# schematic.net
KiCad netlist of a schematic drawn in EAGLE
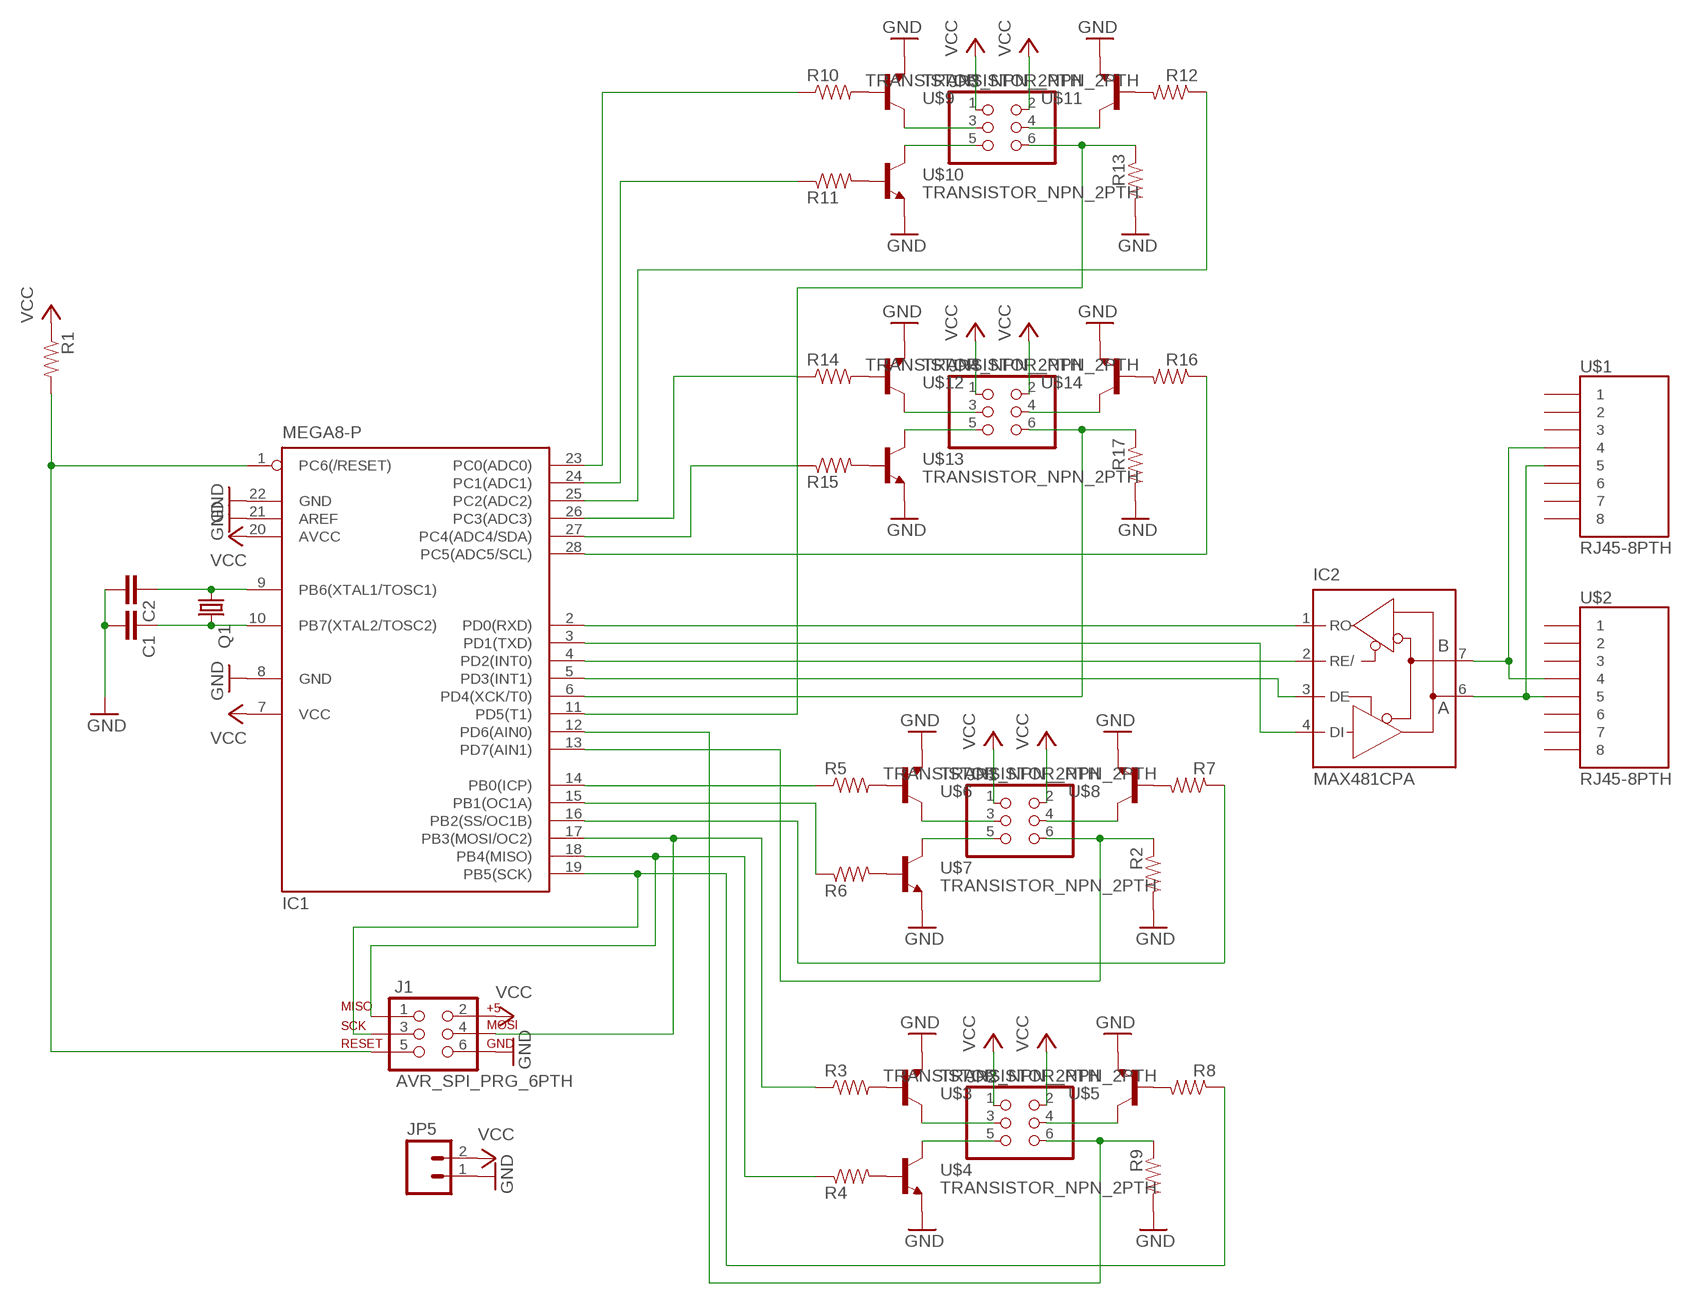
[diagram p0: schematic, sheet 1]

(export (version "E")
  (design (tool "Eeschema 10.0.6"))
  (components
    (comp (ref "C1")
      (value "CAPKIT")
      (footprint "eagle-import:CAP-PTH-SMALL-KIT")
      (libsource (lib "eagle-import") (part "CAPKIT"))
    )
    (comp (ref "C2")
      (value "CAPKIT")
      (footprint "eagle-import:CAP-PTH-SMALL-KIT")
      (libsource (lib "eagle-import") (part "CAPKIT"))
    )
    (comp (ref "IC1")
      (value "MEGA8-P")
      (footprint "eagle-import:DIL28-3")
      (libsource (lib "eagle-import") (part "MEGA8-P"))
    )
    (comp (ref "IC2")
      (value "MAX481CPA")
      (footprint "eagle-import:DIL08")
      (fields (field (name "MPN") "MAX481CPA+"))
      (libsource (lib "eagle-import") (part "MAX481CPA"))
    )
    (comp (ref "J1")
      (value "AVR_SPI_PRG_6PTH")
      (footprint "eagle-import:2X3")
      (libsource (lib "eagle-import") (part "AVR_SPI_PRG_6PTH"))
    )
    (comp (ref "JP1")
      (value "PINHD-2X3")
      (footprint "eagle-import:2X03")
      (libsource (lib "eagle-import") (part "PINHD-2X3"))
    )
    (comp (ref "JP2")
      (value "PINHD-2X3")
      (footprint "eagle-import:2X03")
      (libsource (lib "eagle-import") (part "PINHD-2X3"))
    )
    (comp (ref "JP3")
      (value "PINHD-2X3")
      (footprint "eagle-import:2X03")
      (libsource (lib "eagle-import") (part "PINHD-2X3"))
    )
    (comp (ref "JP4")
      (value "PINHD-2X3")
      (footprint "eagle-import:2X03")
      (libsource (lib "eagle-import") (part "PINHD-2X3"))
    )
    (comp (ref "JP5")
      (value "M023.5MM")
      (footprint "eagle-import:SCREWTERMINAL-3.5MM-2")
      (libsource (lib "eagle-import") (part "M023.5MM"))
    )
    (comp (ref "Q1")
      (value "CRYSTALHC49U-V")
      (footprint "eagle-import:HC49U-V")
      (libsource (lib "eagle-import") (part "CRYSTALHC49U-V"))
    )
    (comp (ref "R1")
      (value "RESISTORPTH-1/4W")
      (footprint "eagle-import:AXIAL-0.4")
      (libsource (lib "eagle-import") (part "RESISTORPTH-1/4W"))
    )
    (comp (ref "R2")
      (value "RESISTORPTH-1/4W")
      (footprint "eagle-import:AXIAL-0.4")
      (libsource (lib "eagle-import") (part "RESISTORPTH-1/4W"))
    )
    (comp (ref "R3")
      (value "RESISTORPTH-1/4W")
      (footprint "eagle-import:AXIAL-0.4")
      (libsource (lib "eagle-import") (part "RESISTORPTH-1/4W"))
    )
    (comp (ref "R4")
      (value "RESISTORPTH-1/4W")
      (footprint "eagle-import:AXIAL-0.4")
      (libsource (lib "eagle-import") (part "RESISTORPTH-1/4W"))
    )
    (comp (ref "R5")
      (value "RESISTORPTH-1/4W")
      (footprint "eagle-import:AXIAL-0.4")
      (libsource (lib "eagle-import") (part "RESISTORPTH-1/4W"))
    )
    (comp (ref "R6")
      (value "RESISTORPTH-1/4W")
      (footprint "eagle-import:AXIAL-0.4")
      (libsource (lib "eagle-import") (part "RESISTORPTH-1/4W"))
    )
    (comp (ref "R7")
      (value "RESISTORPTH-1/4W")
      (footprint "eagle-import:AXIAL-0.4")
      (libsource (lib "eagle-import") (part "RESISTORPTH-1/4W"))
    )
    (comp (ref "R8")
      (value "RESISTORPTH-1/4W")
      (footprint "eagle-import:AXIAL-0.4")
      (libsource (lib "eagle-import") (part "RESISTORPTH-1/4W"))
    )
    (comp (ref "R9")
      (value "RESISTORPTH-1/4W")
      (footprint "eagle-import:AXIAL-0.4")
      (libsource (lib "eagle-import") (part "RESISTORPTH-1/4W"))
    )
    (comp (ref "R10")
      (value "RESISTORPTH-1/4W")
      (footprint "eagle-import:AXIAL-0.4")
      (libsource (lib "eagle-import") (part "RESISTORPTH-1/4W"))
    )
    (comp (ref "R11")
      (value "RESISTORPTH-1/4W")
      (footprint "eagle-import:AXIAL-0.4")
      (libsource (lib "eagle-import") (part "RESISTORPTH-1/4W"))
    )
    (comp (ref "R12")
      (value "RESISTORPTH-1/4W")
      (footprint "eagle-import:AXIAL-0.4")
      (libsource (lib "eagle-import") (part "RESISTORPTH-1/4W"))
    )
    (comp (ref "R13")
      (value "RESISTORPTH-1/4W")
      (footprint "eagle-import:AXIAL-0.4")
      (libsource (lib "eagle-import") (part "RESISTORPTH-1/4W"))
    )
    (comp (ref "R14")
      (value "RESISTORPTH-1/4W")
      (footprint "eagle-import:AXIAL-0.4")
      (libsource (lib "eagle-import") (part "RESISTORPTH-1/4W"))
    )
    (comp (ref "R15")
      (value "RESISTORPTH-1/4W")
      (footprint "eagle-import:AXIAL-0.4")
      (libsource (lib "eagle-import") (part "RESISTORPTH-1/4W"))
    )
    (comp (ref "R16")
      (value "RESISTORPTH-1/4W")
      (footprint "eagle-import:AXIAL-0.4")
      (libsource (lib "eagle-import") (part "RESISTORPTH-1/4W"))
    )
    (comp (ref "R17")
      (value "RESISTORPTH-1/4W")
      (footprint "eagle-import:AXIAL-0.4")
      (libsource (lib "eagle-import") (part "RESISTORPTH-1/4W"))
    )
    (comp (ref "U$1")
      (value "RJ45-8PTH")
      (footprint "eagle-import:RJ45-8")
      (libsource (lib "eagle-import") (part "RJ45-8PTH"))
    )
    (comp (ref "U$2")
      (value "RJ45-8PTH")
      (footprint "eagle-import:RJ45-8")
      (libsource (lib "eagle-import") (part "RJ45-8PTH"))
    )
    (comp (ref "U$3")
      (value "TRANSISTOR_NPN_2PTH")
      (footprint "eagle-import:TO-92")
      (libsource (lib "eagle-import") (part "TRANSISTOR_NPN_2PTH"))
    )
    (comp (ref "U$4")
      (value "TRANSISTOR_NPN_2PTH")
      (footprint "eagle-import:TO-92")
      (libsource (lib "eagle-import") (part "TRANSISTOR_NPN_2PTH"))
    )
    (comp (ref "U$5")
      (value "TRANSISTOR_NPN_2PTH")
      (footprint "eagle-import:TO-92")
      (libsource (lib "eagle-import") (part "TRANSISTOR_NPN_2PTH"))
    )
    (comp (ref "U$6")
      (value "TRANSISTOR_NPN_2PTH")
      (footprint "eagle-import:TO-92")
      (libsource (lib "eagle-import") (part "TRANSISTOR_NPN_2PTH"))
    )
    (comp (ref "U$7")
      (value "TRANSISTOR_NPN_2PTH")
      (footprint "eagle-import:TO-92")
      (libsource (lib "eagle-import") (part "TRANSISTOR_NPN_2PTH"))
    )
    (comp (ref "U$8")
      (value "TRANSISTOR_NPN_2PTH")
      (footprint "eagle-import:TO-92")
      (libsource (lib "eagle-import") (part "TRANSISTOR_NPN_2PTH"))
    )
    (comp (ref "U$9")
      (value "TRANSISTOR_NPN_2PTH")
      (footprint "eagle-import:TO-92")
      (libsource (lib "eagle-import") (part "TRANSISTOR_NPN_2PTH"))
    )
    (comp (ref "U$10")
      (value "TRANSISTOR_NPN_2PTH")
      (footprint "eagle-import:TO-92")
      (libsource (lib "eagle-import") (part "TRANSISTOR_NPN_2PTH"))
    )
    (comp (ref "U$11")
      (value "TRANSISTOR_NPN_2PTH")
      (footprint "eagle-import:TO-92")
      (libsource (lib "eagle-import") (part "TRANSISTOR_NPN_2PTH"))
    )
    (comp (ref "U$12")
      (value "TRANSISTOR_NPN_2PTH")
      (footprint "eagle-import:TO-92")
      (libsource (lib "eagle-import") (part "TRANSISTOR_NPN_2PTH"))
    )
    (comp (ref "U$13")
      (value "TRANSISTOR_NPN_2PTH")
      (footprint "eagle-import:TO-92")
      (libsource (lib "eagle-import") (part "TRANSISTOR_NPN_2PTH"))
    )
    (comp (ref "U$14")
      (value "TRANSISTOR_NPN_2PTH")
      (footprint "eagle-import:TO-92")
      (libsource (lib "eagle-import") (part "TRANSISTOR_NPN_2PTH"))
    )
  )
  (nets
    (net (code "1") (name "GND") (class "Default")
      (node (ref "C1") (pin "2") (pinfunction "2_2") (pintype "passive"))
      (node (ref "C2") (pin "2") (pinfunction "2_2") (pintype "passive"))
      (node (ref "IC1") (pin "21") (pinfunction "AREF_21") (pintype "passive"))
      (node (ref "IC1") (pin "22") (pinfunction "GND_22") (pintype "power_in"))
      (node (ref "IC1") (pin "8") (pinfunction "GND_8") (pintype "power_in"))
      (node (ref "J1") (pin "6") (pinfunction "6_6") (pintype "passive"))
      (node (ref "JP5") (pin "1") (pinfunction "1_1") (pintype "passive"))
      (node (ref "R13") (pin "P$2") (pinfunction "2_P$2") (pintype "passive"))
      (node (ref "R17") (pin "P$2") (pinfunction "2_P$2") (pintype "passive"))
      (node (ref "R2") (pin "P$2") (pinfunction "2_P$2") (pintype "passive"))
      (node (ref "R9") (pin "P$2") (pinfunction "2_P$2") (pintype "passive"))
      (node (ref "U$10") (pin "3") (pinfunction "E_3") (pintype "passive"))
      (node (ref "U$11") (pin "3") (pinfunction "E_3") (pintype "passive"))
      (node (ref "U$12") (pin "3") (pinfunction "E_3") (pintype "passive"))
      (node (ref "U$13") (pin "3") (pinfunction "E_3") (pintype "passive"))
      (node (ref "U$14") (pin "3") (pinfunction "E_3") (pintype "passive"))
      (node (ref "U$3") (pin "3") (pinfunction "E_3") (pintype "passive"))
      (node (ref "U$4") (pin "3") (pinfunction "E_3") (pintype "passive"))
      (node (ref "U$5") (pin "3") (pinfunction "E_3") (pintype "passive"))
      (node (ref "U$6") (pin "3") (pinfunction "E_3") (pintype "passive"))
      (node (ref "U$7") (pin "3") (pinfunction "E_3") (pintype "passive"))
      (node (ref "U$8") (pin "3") (pinfunction "E_3") (pintype "passive"))
      (node (ref "U$9") (pin "3") (pinfunction "E_3") (pintype "passive"))
    )
    (net (code "2") (name "Net-(IC1-PB0(ICP))") (class "Default")
      (node (ref "IC1") (pin "14") (pinfunction "PB0(ICP)_14") (pintype "bidirectional"))
      (node (ref "R5") (pin "P$1") (pinfunction "1_P$1") (pintype "passive"))
    )
    (net (code "3") (name "Net-(IC1-PB1(OC1A))") (class "Default")
      (node (ref "IC1") (pin "15") (pinfunction "PB1(OC1A)_15") (pintype "bidirectional"))
      (node (ref "R6") (pin "P$1") (pinfunction "1_P$1") (pintype "passive"))
    )
    (net (code "4") (name "Net-(IC1-PB2(SS{slash}OC1B))") (class "Default")
      (node (ref "IC1") (pin "16") (pinfunction "PB2(SS/OC1B)_16") (pintype "bidirectional"))
      (node (ref "R7") (pin "P$1") (pinfunction "1_P$1") (pintype "passive"))
    )
    (net (code "5") (name "Net-(IC1-PB3(MOSI{slash}OC2))") (class "Default")
      (node (ref "IC1") (pin "17") (pinfunction "PB3(MOSI/OC2)_17") (pintype "bidirectional"))
      (node (ref "J1") (pin "4") (pinfunction "4_4") (pintype "passive"))
      (node (ref "R3") (pin "P$1") (pinfunction "1_P$1") (pintype "passive"))
    )
    (net (code "6") (name "Net-(IC1-PB4(MISO))") (class "Default")
      (node (ref "IC1") (pin "18") (pinfunction "PB4(MISO)_18") (pintype "bidirectional"))
      (node (ref "J1") (pin "1") (pinfunction "1_1") (pintype "passive"))
      (node (ref "R4") (pin "P$1") (pinfunction "1_P$1") (pintype "passive"))
    )
    (net (code "7") (name "Net-(IC1-PB5(SCK))") (class "Default")
      (node (ref "IC1") (pin "19") (pinfunction "PB5(SCK)_19") (pintype "bidirectional"))
      (node (ref "J1") (pin "3") (pinfunction "3_3") (pintype "passive"))
      (node (ref "R8") (pin "P$1") (pinfunction "1_P$1") (pintype "passive"))
    )
    (net (code "8") (name "Net-(IC1-PB6(XTAL1{slash}TOSC1))") (class "Default")
      (node (ref "C2") (pin "1") (pinfunction "1_1") (pintype "passive"))
      (node (ref "IC1") (pin "9") (pinfunction "PB6(XTAL1/TOSC1)_9") (pintype "bidirectional"))
      (node (ref "Q1") (pin "1") (pinfunction "1_1") (pintype "passive"))
    )
    (net (code "9") (name "Net-(IC1-PB7(XTAL2{slash}TOSC2))") (class "Default")
      (node (ref "C1") (pin "1") (pinfunction "1_1") (pintype "passive"))
      (node (ref "IC1") (pin "10") (pinfunction "PB7(XTAL2/TOSC2)_10") (pintype "bidirectional"))
      (node (ref "Q1") (pin "2") (pinfunction "2_2") (pintype "passive"))
    )
    (net (code "10") (name "Net-(IC1-PC0(ADC0))") (class "Default")
      (node (ref "IC1") (pin "23") (pinfunction "PC0(ADC0)_23") (pintype "bidirectional"))
      (node (ref "R10") (pin "P$1") (pinfunction "1_P$1") (pintype "passive"))
    )
    (net (code "11") (name "Net-(IC1-PC1(ADC1))") (class "Default")
      (node (ref "IC1") (pin "24") (pinfunction "PC1(ADC1)_24") (pintype "bidirectional"))
      (node (ref "R11") (pin "P$1") (pinfunction "1_P$1") (pintype "passive"))
    )
    (net (code "12") (name "Net-(IC1-PC2(ADC2))") (class "Default")
      (node (ref "IC1") (pin "25") (pinfunction "PC2(ADC2)_25") (pintype "bidirectional"))
      (node (ref "R12") (pin "P$1") (pinfunction "1_P$1") (pintype "passive"))
    )
    (net (code "13") (name "Net-(IC1-PC3(ADC3))") (class "Default")
      (node (ref "IC1") (pin "26") (pinfunction "PC3(ADC3)_26") (pintype "bidirectional"))
      (node (ref "R14") (pin "P$1") (pinfunction "1_P$1") (pintype "passive"))
    )
    (net (code "14") (name "Net-(IC1-PC4(ADC4{slash}SDA))") (class "Default")
      (node (ref "IC1") (pin "27") (pinfunction "PC4(ADC4/SDA)_27") (pintype "bidirectional"))
      (node (ref "R15") (pin "P$1") (pinfunction "1_P$1") (pintype "passive"))
    )
    (net (code "15") (name "Net-(IC1-PC5(ADC5{slash}SCL))") (class "Default")
      (node (ref "IC1") (pin "28") (pinfunction "PC5(ADC5/SCL)_28") (pintype "bidirectional"))
      (node (ref "R16") (pin "P$1") (pinfunction "1_P$1") (pintype "passive"))
    )
    (net (code "16") (name "Net-(IC1-PC6({slash}RESET))") (class "Default")
      (node (ref "IC1") (pin "1") (pinfunction "PC6(/RESET)_1") (pintype "bidirectional"))
      (node (ref "J1") (pin "5") (pinfunction "5_5") (pintype "passive"))
      (node (ref "R1") (pin "P$2") (pinfunction "2_P$2") (pintype "passive"))
    )
    (net (code "17") (name "Net-(IC1-PD0(RXD))") (class "Default")
      (node (ref "IC1") (pin "2") (pinfunction "PD0(RXD)_2") (pintype "bidirectional"))
      (node (ref "IC2") (pin "1") (pinfunction "RO_1") (pintype "output"))
    )
    (net (code "18") (name "Net-(IC1-PD1(TXD))") (class "Default")
      (node (ref "IC1") (pin "3") (pinfunction "PD1(TXD)_3") (pintype "bidirectional"))
      (node (ref "IC2") (pin "4") (pinfunction "DI_4") (pintype "input"))
    )
    (net (code "19") (name "Net-(IC1-PD2(INT0))") (class "Default")
      (node (ref "IC1") (pin "4") (pinfunction "PD2(INT0)_4") (pintype "bidirectional"))
      (node (ref "IC2") (pin "2") (pinfunction "RE/_2") (pintype "input"))
    )
    (net (code "20") (name "Net-(IC1-PD3(INT1))") (class "Default")
      (node (ref "IC1") (pin "5") (pinfunction "PD3(INT1)_5") (pintype "bidirectional"))
      (node (ref "IC2") (pin "3") (pinfunction "DE_3") (pintype "input"))
    )
    (net (code "21") (name "Net-(IC1-PD4(XCK{slash}T0))") (class "Default")
      (node (ref "IC1") (pin "6") (pinfunction "PD4(XCK/T0)_6") (pintype "bidirectional"))
      (node (ref "JP4") (pin "6") (pinfunction "6_6") (pintype "passive"))
      (node (ref "R17") (pin "P$1") (pinfunction "1_P$1") (pintype "passive"))
    )
    (net (code "22") (name "Net-(IC1-PD5(T1))") (class "Default")
      (node (ref "IC1") (pin "11") (pinfunction "PD5(T1)_11") (pintype "bidirectional"))
      (node (ref "JP3") (pin "6") (pinfunction "6_6") (pintype "passive"))
      (node (ref "R13") (pin "P$1") (pinfunction "1_P$1") (pintype "passive"))
    )
    (net (code "23") (name "Net-(IC1-PD6(AIN0))") (class "Default")
      (node (ref "IC1") (pin "12") (pinfunction "PD6(AIN0)_12") (pintype "bidirectional"))
      (node (ref "JP2") (pin "6") (pinfunction "6_6") (pintype "passive"))
      (node (ref "R9") (pin "P$1") (pinfunction "1_P$1") (pintype "passive"))
    )
    (net (code "24") (name "Net-(IC1-PD7(AIN1))") (class "Default")
      (node (ref "IC1") (pin "13") (pinfunction "PD7(AIN1)_13") (pintype "bidirectional"))
      (node (ref "JP1") (pin "6") (pinfunction "6_6") (pintype "passive"))
      (node (ref "R2") (pin "P$1") (pinfunction "1_P$1") (pintype "passive"))
    )
    (net (code "25") (name "Net-(IC2A-A)") (class "Default")
      (node (ref "IC2") (pin "6") (pinfunction "A_6") (pintype "passive"))
      (node (ref "U$1") (pin "5") (pinfunction "5_5") (pintype "bidirectional"))
      (node (ref "U$2") (pin "5") (pinfunction "5_5") (pintype "bidirectional"))
    )
    (net (code "26") (name "Net-(IC2A-B)") (class "Default")
      (node (ref "IC2") (pin "7") (pinfunction "B_7") (pintype "passive"))
      (node (ref "U$1") (pin "4") (pinfunction "4_4") (pintype "bidirectional"))
      (node (ref "U$2") (pin "4") (pinfunction "4_4") (pintype "bidirectional"))
    )
    (net (code "27") (name "Net-(R3-2)") (class "Default")
      (node (ref "R3") (pin "P$2") (pinfunction "2_P$2") (pintype "passive"))
      (node (ref "U$3") (pin "2") (pinfunction "B_2") (pintype "passive"))
    )
    (net (code "28") (name "Net-(R4-2)") (class "Default")
      (node (ref "R4") (pin "P$2") (pinfunction "2_P$2") (pintype "passive"))
      (node (ref "U$4") (pin "2") (pinfunction "B_2") (pintype "passive"))
    )
    (net (code "29") (name "Net-(R5-2)") (class "Default")
      (node (ref "R5") (pin "P$2") (pinfunction "2_P$2") (pintype "passive"))
      (node (ref "U$6") (pin "2") (pinfunction "B_2") (pintype "passive"))
    )
    (net (code "30") (name "Net-(R6-2)") (class "Default")
      (node (ref "R6") (pin "P$2") (pinfunction "2_P$2") (pintype "passive"))
      (node (ref "U$7") (pin "2") (pinfunction "B_2") (pintype "passive"))
    )
    (net (code "31") (name "Net-(R7-2)") (class "Default")
      (node (ref "R7") (pin "P$2") (pinfunction "2_P$2") (pintype "passive"))
      (node (ref "U$8") (pin "2") (pinfunction "B_2") (pintype "passive"))
    )
    (net (code "32") (name "Net-(R8-2)") (class "Default")
      (node (ref "R8") (pin "P$2") (pinfunction "2_P$2") (pintype "passive"))
      (node (ref "U$5") (pin "2") (pinfunction "B_2") (pintype "passive"))
    )
    (net (code "33") (name "Net-(R10-2)") (class "Default")
      (node (ref "R10") (pin "P$2") (pinfunction "2_P$2") (pintype "passive"))
      (node (ref "U$9") (pin "2") (pinfunction "B_2") (pintype "passive"))
    )
    (net (code "34") (name "Net-(R11-2)") (class "Default")
      (node (ref "R11") (pin "P$2") (pinfunction "2_P$2") (pintype "passive"))
      (node (ref "U$10") (pin "2") (pinfunction "B_2") (pintype "passive"))
    )
    (net (code "35") (name "Net-(R12-2)") (class "Default")
      (node (ref "R12") (pin "P$2") (pinfunction "2_P$2") (pintype "passive"))
      (node (ref "U$11") (pin "2") (pinfunction "B_2") (pintype "passive"))
    )
    (net (code "36") (name "Net-(R14-2)") (class "Default")
      (node (ref "R14") (pin "P$2") (pinfunction "2_P$2") (pintype "passive"))
      (node (ref "U$12") (pin "2") (pinfunction "B_2") (pintype "passive"))
    )
    (net (code "37") (name "Net-(R15-2)") (class "Default")
      (node (ref "R15") (pin "P$2") (pinfunction "2_P$2") (pintype "passive"))
      (node (ref "U$13") (pin "2") (pinfunction "B_2") (pintype "passive"))
    )
    (net (code "38") (name "Net-(R16-2)") (class "Default")
      (node (ref "R16") (pin "P$2") (pinfunction "2_P$2") (pintype "passive"))
      (node (ref "U$14") (pin "2") (pinfunction "B_2") (pintype "passive"))
    )
    (net (code "39") (name "Net-(U$3-C)") (class "Default")
      (node (ref "JP2") (pin "3") (pinfunction "3_3") (pintype "passive"))
      (node (ref "U$3") (pin "1") (pinfunction "C_1") (pintype "passive"))
    )
    (net (code "40") (name "Net-(U$4-C)") (class "Default")
      (node (ref "JP2") (pin "5") (pinfunction "5_5") (pintype "passive"))
      (node (ref "U$4") (pin "1") (pinfunction "C_1") (pintype "passive"))
    )
    (net (code "41") (name "Net-(U$5-C)") (class "Default")
      (node (ref "JP2") (pin "4") (pinfunction "4_4") (pintype "passive"))
      (node (ref "U$5") (pin "1") (pinfunction "C_1") (pintype "passive"))
    )
    (net (code "42") (name "Net-(U$6-C)") (class "Default")
      (node (ref "JP1") (pin "3") (pinfunction "3_3") (pintype "passive"))
      (node (ref "U$6") (pin "1") (pinfunction "C_1") (pintype "passive"))
    )
    (net (code "43") (name "Net-(U$7-C)") (class "Default")
      (node (ref "JP1") (pin "5") (pinfunction "5_5") (pintype "passive"))
      (node (ref "U$7") (pin "1") (pinfunction "C_1") (pintype "passive"))
    )
    (net (code "44") (name "Net-(U$8-C)") (class "Default")
      (node (ref "JP1") (pin "4") (pinfunction "4_4") (pintype "passive"))
      (node (ref "U$8") (pin "1") (pinfunction "C_1") (pintype "passive"))
    )
    (net (code "45") (name "Net-(U$9-C)") (class "Default")
      (node (ref "JP3") (pin "3") (pinfunction "3_3") (pintype "passive"))
      (node (ref "U$9") (pin "1") (pinfunction "C_1") (pintype "passive"))
    )
    (net (code "46") (name "Net-(U$10-C)") (class "Default")
      (node (ref "JP3") (pin "5") (pinfunction "5_5") (pintype "passive"))
      (node (ref "U$10") (pin "1") (pinfunction "C_1") (pintype "passive"))
    )
    (net (code "47") (name "Net-(U$11-C)") (class "Default")
      (node (ref "JP3") (pin "4") (pinfunction "4_4") (pintype "passive"))
      (node (ref "U$11") (pin "1") (pinfunction "C_1") (pintype "passive"))
    )
    (net (code "48") (name "Net-(U$12-C)") (class "Default")
      (node (ref "JP4") (pin "3") (pinfunction "3_3") (pintype "passive"))
      (node (ref "U$12") (pin "1") (pinfunction "C_1") (pintype "passive"))
    )
    (net (code "49") (name "Net-(U$13-C)") (class "Default")
      (node (ref "JP4") (pin "5") (pinfunction "5_5") (pintype "passive"))
      (node (ref "U$13") (pin "1") (pinfunction "C_1") (pintype "passive"))
    )
    (net (code "50") (name "Net-(U$14-C)") (class "Default")
      (node (ref "JP4") (pin "4") (pinfunction "4_4") (pintype "passive"))
      (node (ref "U$14") (pin "1") (pinfunction "C_1") (pintype "passive"))
    )
    (net (code "51") (name "VCC") (class "Default")
      (node (ref "IC1") (pin "20") (pinfunction "AVCC_20") (pintype "power_in"))
      (node (ref "IC1") (pin "7") (pinfunction "VCC_7") (pintype "power_in"))
      (node (ref "J1") (pin "2") (pinfunction "2_2") (pintype "passive"))
      (node (ref "JP1") (pin "1") (pinfunction "1_1") (pintype "passive"))
      (node (ref "JP1") (pin "2") (pinfunction "2_2") (pintype "passive"))
      (node (ref "JP2") (pin "1") (pinfunction "1_1") (pintype "passive"))
      (node (ref "JP2") (pin "2") (pinfunction "2_2") (pintype "passive"))
      (node (ref "JP3") (pin "1") (pinfunction "1_1") (pintype "passive"))
      (node (ref "JP3") (pin "2") (pinfunction "2_2") (pintype "passive"))
      (node (ref "JP4") (pin "1") (pinfunction "1_1") (pintype "passive"))
      (node (ref "JP4") (pin "2") (pinfunction "2_2") (pintype "passive"))
      (node (ref "JP5") (pin "2") (pinfunction "2_2") (pintype "passive"))
      (node (ref "R1") (pin "P$1") (pinfunction "1_P$1") (pintype "passive"))
    )
    (net (code "52") (name "unconnected-(U$1-Pad1)") (class "Default")
      (node (ref "U$1") (pin "1") (pinfunction "1_1") (pintype "bidirectional"))
    )
    (net (code "53") (name "unconnected-(U$1-Pad2)") (class "Default")
      (node (ref "U$1") (pin "2") (pinfunction "2_2") (pintype "bidirectional"))
    )
    (net (code "54") (name "unconnected-(U$1-Pad3)") (class "Default")
      (node (ref "U$1") (pin "3") (pinfunction "3_3") (pintype "bidirectional"))
    )
    (net (code "55") (name "unconnected-(U$1-Pad6)") (class "Default")
      (node (ref "U$1") (pin "6") (pinfunction "6_6") (pintype "bidirectional"))
    )
    (net (code "56") (name "unconnected-(U$1-Pad7)") (class "Default")
      (node (ref "U$1") (pin "7") (pinfunction "7_7") (pintype "bidirectional"))
    )
    (net (code "57") (name "unconnected-(U$1-Pad8)") (class "Default")
      (node (ref "U$1") (pin "8") (pinfunction "8_8") (pintype "bidirectional"))
    )
    (net (code "58") (name "unconnected-(U$2-Pad1)") (class "Default")
      (node (ref "U$2") (pin "1") (pinfunction "1_1") (pintype "bidirectional"))
    )
    (net (code "59") (name "unconnected-(U$2-Pad2)") (class "Default")
      (node (ref "U$2") (pin "2") (pinfunction "2_2") (pintype "bidirectional"))
    )
    (net (code "60") (name "unconnected-(U$2-Pad3)") (class "Default")
      (node (ref "U$2") (pin "3") (pinfunction "3_3") (pintype "bidirectional"))
    )
    (net (code "61") (name "unconnected-(U$2-Pad6)") (class "Default")
      (node (ref "U$2") (pin "6") (pinfunction "6_6") (pintype "bidirectional"))
    )
    (net (code "62") (name "unconnected-(U$2-Pad7)") (class "Default")
      (node (ref "U$2") (pin "7") (pinfunction "7_7") (pintype "bidirectional"))
    )
    (net (code "63") (name "unconnected-(U$2-Pad8)") (class "Default")
      (node (ref "U$2") (pin "8") (pinfunction "8_8") (pintype "bidirectional"))
    )
  )
)
